# rocketradio.net
KiCad netlist of a schematic drawn in EAGLE
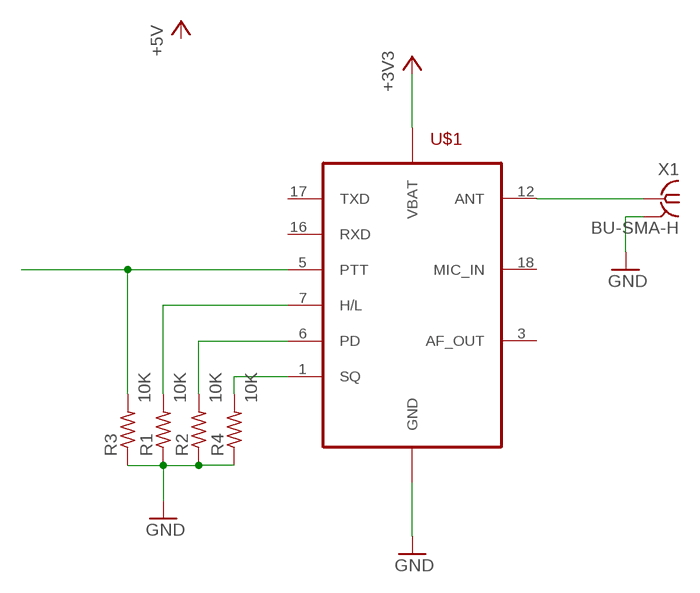
[diagram p0: schematic, sheet 1]

(export (version "E")
  (design (tool "Eeschema 10.0.6"))
  (components
    (comp (ref "R1")
      (value "10K")
      (footprint "eagle-import:R0603")
      (libsource (lib "eagle-import") (part "R-US_R0603"))
    )
    (comp (ref "R2")
      (value "10K")
      (footprint "eagle-import:R0603")
      (libsource (lib "eagle-import") (part "R-US_R0603"))
    )
    (comp (ref "R3")
      (value "10K")
      (footprint "eagle-import:R0603")
      (libsource (lib "eagle-import") (part "R-US_R0603"))
    )
    (comp (ref "R4")
      (value "10K")
      (footprint "eagle-import:R0603")
      (libsource (lib "eagle-import") (part "R-US_R0603"))
    )
    (comp (ref "U$1")
      (value "DORJI")
      (footprint "eagle-import:DORJI")
      (libsource (lib "eagle-import") (part "DORJI"))
    )
    (comp (ref "X1")
      (value "BU-SMA-H")
      (footprint "eagle-import:BU-SMA-H")
      (libsource (lib "eagle-import") (part "BU-SMA-H"))
    )
  )
  (nets
    (net (code "1") (name "+3V3") (class "Default")
      (node (ref "U$1") (pin "8") (pinfunction "VBAT_8") (pintype "bidirectional"))
    )
    (net (code "3") (name "GND") (class "Default")
      (node (ref "R1") (pin "1") (pinfunction "1_1") (pintype "passive"))
      (node (ref "R2") (pin "1") (pinfunction "1_1") (pintype "passive"))
      (node (ref "R3") (pin "1") (pinfunction "1_1") (pintype "passive"))
      (node (ref "R4") (pin "1") (pinfunction "1_1") (pintype "passive"))
      (node (ref "U$1") (pin "10") (pinfunction "GND_10") (pintype "bidirectional"))
      (node (ref "U$1") (pin "9") (pinfunction "GND_9") (pintype "bidirectional"))
      (node (ref "X1") (pin "2") (pinfunction "2_2") (pintype "passive"))
      (node (ref "X1") (pin "3") (pinfunction "2_3") (pintype "passive"))
      (node (ref "X1") (pin "4") (pinfunction "2_4") (pintype "passive"))
      (node (ref "X1") (pin "5") (pinfunction "2_5") (pintype "passive"))
    )
    (net (code "4") (name "Net-(U$1-ANT)") (class "Default")
      (node (ref "U$1") (pin "12") (pinfunction "ANT_12") (pintype "bidirectional"))
      (node (ref "X1") (pin "1") (pinfunction "1_1") (pintype "passive"))
    )
    (net (code "5") (name "Net-(U$1-H{slash}L)") (class "Default")
      (node (ref "R1") (pin "2") (pinfunction "2_2") (pintype "passive"))
      (node (ref "U$1") (pin "7") (pinfunction "H/L_7") (pintype "bidirectional"))
    )
    (net (code "6") (name "Net-(U$1-PD)") (class "Default")
      (node (ref "R2") (pin "2") (pinfunction "2_2") (pintype "passive"))
      (node (ref "U$1") (pin "6") (pinfunction "PD_6") (pintype "bidirectional"))
    )
    (net (code "7") (name "Net-(U$1-PTT)") (class "Default")
      (node (ref "R3") (pin "2") (pinfunction "2_2") (pintype "passive"))
      (node (ref "U$1") (pin "5") (pinfunction "PTT_5") (pintype "bidirectional"))
    )
    (net (code "8") (name "Net-(U$1-SQ)") (class "Default")
      (node (ref "R4") (pin "2") (pinfunction "2_2") (pintype "passive"))
      (node (ref "U$1") (pin "1") (pinfunction "SQ_1") (pintype "bidirectional"))
    )
    (net (code "9") (name "unconnected-(U$1-AF_OUT-Pad3)") (class "Default")
      (node (ref "U$1") (pin "3") (pinfunction "AF_OUT_3") (pintype "bidirectional"))
    )
    (net (code "10") (name "unconnected-(U$1-MIC_IN-Pad18)") (class "Default")
      (node (ref "U$1") (pin "18") (pinfunction "MIC_IN_18") (pintype "bidirectional"))
    )
    (net (code "11") (name "unconnected-(U$1-RXD-Pad16)") (class "Default")
      (node (ref "U$1") (pin "16") (pinfunction "RXD_16") (pintype "bidirectional"))
    )
    (net (code "12") (name "unconnected-(U$1-TXD-Pad17)") (class "Default")
      (node (ref "U$1") (pin "17") (pinfunction "TXD_17") (pintype "bidirectional"))
    )
  )
)
